# counter.net
KiCad netlist of a schematic drawn in EAGLE
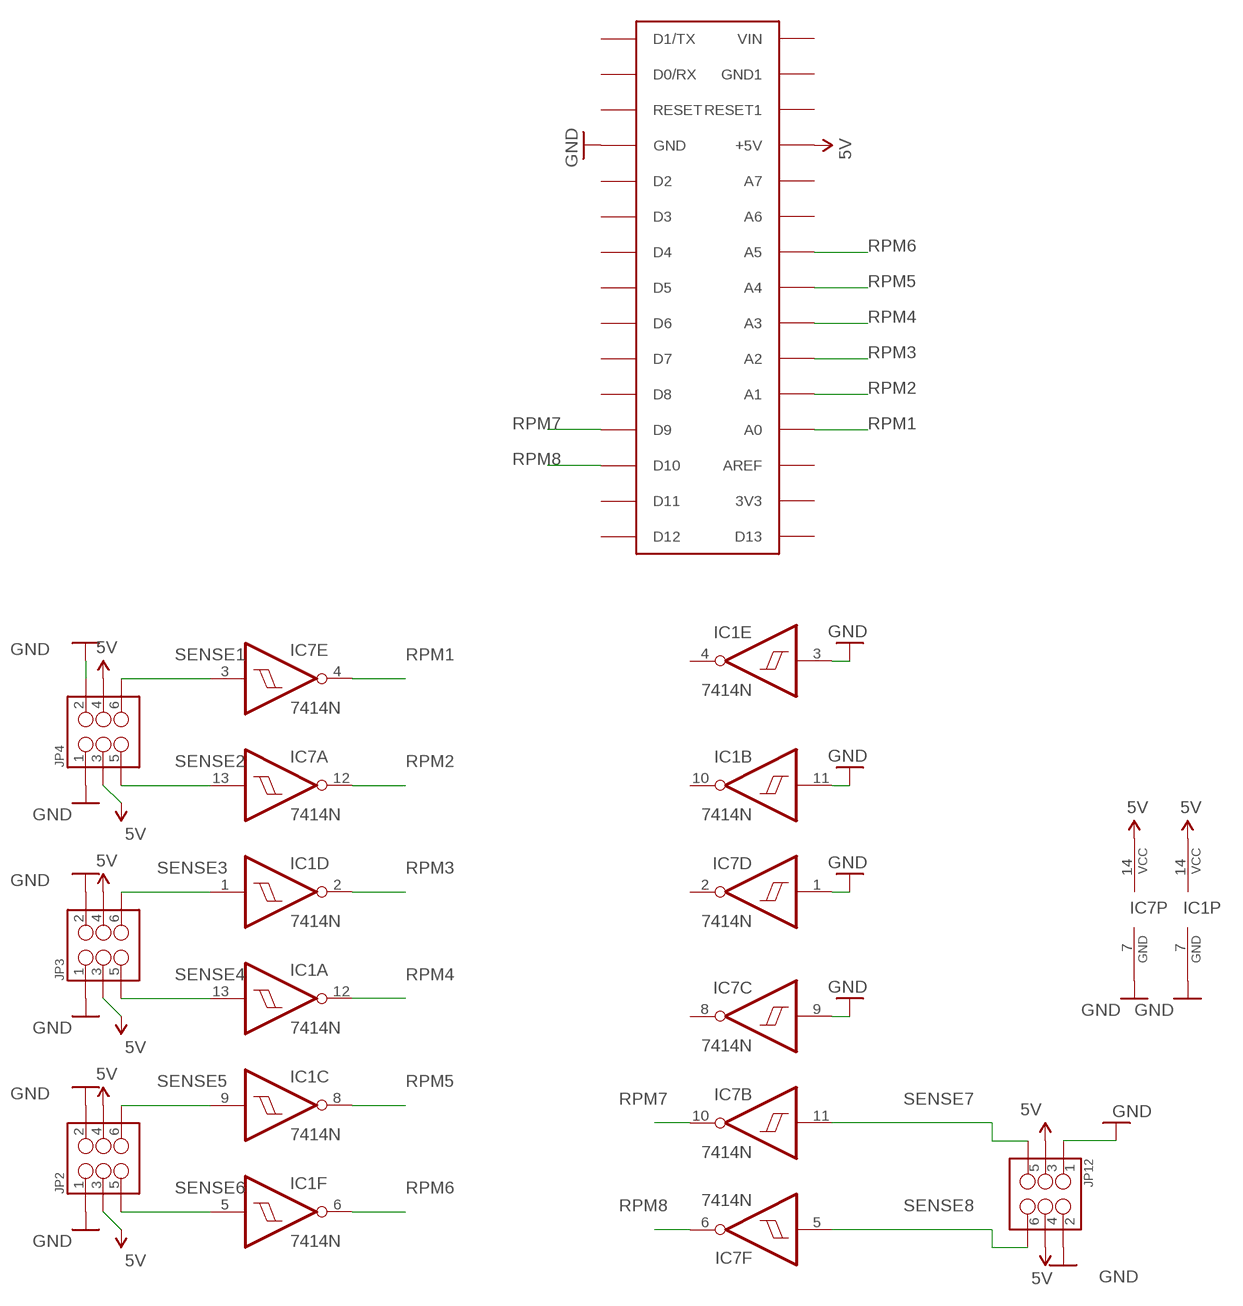
[diagram p0: schematic, sheet 1]

(export (version "E")
  (design (tool "Eeschema 10.0.6"))
  (components
    (comp (ref "IC1")
      (value "7414N")
      (footprint "eagle-import:DIL14")
      (libsource (lib "eagle-import") (part "7414N"))
    )
    (comp (ref "IC7")
      (value "7414N")
      (footprint "eagle-import:DIL14")
      (libsource (lib "eagle-import") (part "7414N"))
    )
    (comp (ref "JP2")
      (value "M03X2NO_SILK")
      (footprint "eagle-import:2X3-NS")
      (libsource (lib "eagle-import") (part "M03X2NO_SILK"))
    )
    (comp (ref "JP3")
      (value "M03X2NO_SILK")
      (footprint "eagle-import:2X3-NS")
      (libsource (lib "eagle-import") (part "M03X2NO_SILK"))
    )
    (comp (ref "JP4")
      (value "M03X2NO_SILK")
      (footprint "eagle-import:2X3-NS")
      (libsource (lib "eagle-import") (part "M03X2NO_SILK"))
    )
    (comp (ref "JP12")
      (value "M03X2NO_SILK")
      (footprint "eagle-import:2X3-NS")
      (libsource (lib "eagle-import") (part "M03X2NO_SILK"))
    )
    (comp (ref "U$1")
      (value "ARDUINONANO")
      (footprint "eagle-import:PDIP-32")
      (libsource (lib "eagle-import") (part "ARDUINONANO"))
    )
  )
  (nets
    (net (code "1") (name "/RPM1") (class "Default")
      (node (ref "IC7") (pin "4") (pinfunction "O_4") (pintype "output"))
      (node (ref "U$1") (pin "A0") (pinfunction "A0_A0") (pintype "bidirectional"))
    )
    (net (code "2") (name "/RPM2") (class "Default")
      (node (ref "IC7") (pin "12") (pinfunction "O_12") (pintype "output"))
      (node (ref "U$1") (pin "A1") (pinfunction "A1_A1") (pintype "bidirectional"))
    )
    (net (code "3") (name "/RPM3") (class "Default")
      (node (ref "IC1") (pin "2") (pinfunction "O_2") (pintype "output"))
      (node (ref "U$1") (pin "A2") (pinfunction "A2_A2") (pintype "bidirectional"))
    )
    (net (code "4") (name "/RPM4") (class "Default")
      (node (ref "IC1") (pin "12") (pinfunction "O_12") (pintype "output"))
      (node (ref "U$1") (pin "A3") (pinfunction "A3_A3") (pintype "bidirectional"))
    )
    (net (code "5") (name "/RPM5") (class "Default")
      (node (ref "IC1") (pin "8") (pinfunction "O_8") (pintype "output"))
      (node (ref "U$1") (pin "A4") (pinfunction "A4_A4") (pintype "bidirectional"))
    )
    (net (code "6") (name "/RPM6") (class "Default")
      (node (ref "IC1") (pin "6") (pinfunction "O_6") (pintype "output"))
      (node (ref "U$1") (pin "A5") (pinfunction "A5_A5") (pintype "bidirectional"))
    )
    (net (code "7") (name "/RPM7") (class "Default")
      (node (ref "IC7") (pin "10") (pinfunction "O_10") (pintype "output"))
      (node (ref "U$1") (pin "D9") (pinfunction "D9_D9") (pintype "bidirectional"))
    )
    (net (code "8") (name "/RPM8") (class "Default")
      (node (ref "IC7") (pin "6") (pinfunction "O_6") (pintype "output"))
      (node (ref "U$1") (pin "D10") (pinfunction "D10_D10") (pintype "bidirectional"))
    )
    (net (code "9") (name "/SENSE1") (class "Default")
      (node (ref "IC7") (pin "3") (pinfunction "I_3") (pintype "input"))
      (node (ref "JP4") (pin "6") (pinfunction "6_6") (pintype "bidirectional"))
    )
    (net (code "10") (name "/SENSE2") (class "Default")
      (node (ref "IC7") (pin "13") (pinfunction "I_13") (pintype "input"))
      (node (ref "JP4") (pin "5") (pinfunction "5_5") (pintype "bidirectional"))
    )
    (net (code "11") (name "/SENSE3") (class "Default")
      (node (ref "IC1") (pin "1") (pinfunction "I_1") (pintype "input"))
      (node (ref "JP3") (pin "6") (pinfunction "6_6") (pintype "bidirectional"))
    )
    (net (code "12") (name "/SENSE4") (class "Default")
      (node (ref "IC1") (pin "13") (pinfunction "I_13") (pintype "input"))
      (node (ref "JP3") (pin "5") (pinfunction "5_5") (pintype "bidirectional"))
    )
    (net (code "13") (name "/SENSE5") (class "Default")
      (node (ref "IC1") (pin "9") (pinfunction "I_9") (pintype "input"))
      (node (ref "JP2") (pin "6") (pinfunction "6_6") (pintype "bidirectional"))
    )
    (net (code "14") (name "/SENSE6") (class "Default")
      (node (ref "IC1") (pin "5") (pinfunction "I_5") (pintype "input"))
      (node (ref "JP2") (pin "5") (pinfunction "5_5") (pintype "bidirectional"))
    )
    (net (code "15") (name "/SENSE7") (class "Default")
      (node (ref "IC7") (pin "11") (pinfunction "I_11") (pintype "input"))
      (node (ref "JP12") (pin "5") (pinfunction "5_5") (pintype "bidirectional"))
    )
    (net (code "16") (name "/SENSE8") (class "Default")
      (node (ref "IC7") (pin "5") (pinfunction "I_5") (pintype "input"))
      (node (ref "JP12") (pin "6") (pinfunction "6_6") (pintype "bidirectional"))
    )
    (net (code "17") (name "5V") (class "Default")
      (node (ref "IC1") (pin "14") (pinfunction "VCC_14") (pintype "power_in"))
      (node (ref "IC7") (pin "14") (pinfunction "VCC_14") (pintype "power_in"))
      (node (ref "JP12") (pin "3") (pinfunction "3_3") (pintype "bidirectional"))
      (node (ref "JP12") (pin "4") (pinfunction "4_4") (pintype "bidirectional"))
      (node (ref "JP2") (pin "3") (pinfunction "3_3") (pintype "bidirectional"))
      (node (ref "JP2") (pin "4") (pinfunction "4_4") (pintype "bidirectional"))
      (node (ref "JP3") (pin "3") (pinfunction "3_3") (pintype "bidirectional"))
      (node (ref "JP3") (pin "4") (pinfunction "4_4") (pintype "bidirectional"))
      (node (ref "JP4") (pin "3") (pinfunction "3_3") (pintype "bidirectional"))
      (node (ref "JP4") (pin "4") (pinfunction "4_4") (pintype "bidirectional"))
      (node (ref "U$1") (pin "+5V") (pinfunction "+5V_+5V") (pintype "bidirectional"))
    )
    (net (code "18") (name "GND") (class "Default")
      (node (ref "IC1") (pin "11") (pinfunction "I_11") (pintype "input"))
      (node (ref "IC1") (pin "3") (pinfunction "I_3") (pintype "input"))
      (node (ref "IC1") (pin "7") (pinfunction "GND_7") (pintype "power_in"))
      (node (ref "IC7") (pin "1") (pinfunction "I_1") (pintype "input"))
      (node (ref "IC7") (pin "7") (pinfunction "GND_7") (pintype "power_in"))
      (node (ref "IC7") (pin "9") (pinfunction "I_9") (pintype "input"))
      (node (ref "JP12") (pin "1") (pinfunction "1_1") (pintype "bidirectional"))
      (node (ref "JP12") (pin "2") (pinfunction "2_2") (pintype "bidirectional"))
      (node (ref "JP2") (pin "1") (pinfunction "1_1") (pintype "bidirectional"))
      (node (ref "JP2") (pin "2") (pinfunction "2_2") (pintype "bidirectional"))
      (node (ref "JP3") (pin "1") (pinfunction "1_1") (pintype "bidirectional"))
      (node (ref "JP3") (pin "2") (pinfunction "2_2") (pintype "bidirectional"))
      (node (ref "JP4") (pin "1") (pinfunction "1_1") (pintype "bidirectional"))
      (node (ref "JP4") (pin "2") (pinfunction "2_2") (pintype "bidirectional"))
      (node (ref "U$1") (pin "GND") (pinfunction "GND_GND") (pintype "bidirectional"))
    )
    (net (code "19") (name "unconnected-(IC1B-O-Pad10)") (class "Default")
      (node (ref "IC1") (pin "10") (pinfunction "O_10") (pintype "output"))
    )
    (net (code "20") (name "unconnected-(IC1E-O-Pad4)") (class "Default")
      (node (ref "IC1") (pin "4") (pinfunction "O_4") (pintype "output"))
    )
    (net (code "21") (name "unconnected-(IC7C-O-Pad8)") (class "Default")
      (node (ref "IC7") (pin "8") (pinfunction "O_8") (pintype "output"))
    )
    (net (code "22") (name "unconnected-(IC7D-O-Pad2)") (class "Default")
      (node (ref "IC7") (pin "2") (pinfunction "O_2") (pintype "output"))
    )
    (net (code "23") (name "unconnected-(U$1-Pad3V3)") (class "Default")
      (node (ref "U$1") (pin "3V3") (pinfunction "3V3_3V3") (pintype "bidirectional"))
    )
    (net (code "24") (name "unconnected-(U$1-PadA6)") (class "Default")
      (node (ref "U$1") (pin "A6") (pinfunction "A6_A6") (pintype "bidirectional"))
    )
    (net (code "25") (name "unconnected-(U$1-PadA7)") (class "Default")
      (node (ref "U$1") (pin "A7") (pinfunction "A7_A7") (pintype "bidirectional"))
    )
    (net (code "26") (name "unconnected-(U$1-PadAREF)") (class "Default")
      (node (ref "U$1") (pin "AREF") (pinfunction "AREF_AREF") (pintype "bidirectional"))
    )
    (net (code "27") (name "unconnected-(U$1-PadD0{slash}RX)") (class "Default")
      (node (ref "U$1") (pin "D0/RX") (pinfunction "D0/RX_D0/RX") (pintype "bidirectional"))
    )
    (net (code "28") (name "unconnected-(U$1-PadD1{slash}TX)") (class "Default")
      (node (ref "U$1") (pin "D1/TX") (pinfunction "D1/TX_D1/TX") (pintype "bidirectional"))
    )
    (net (code "29") (name "unconnected-(U$1-PadD2)") (class "Default")
      (node (ref "U$1") (pin "D2") (pinfunction "D2_D2") (pintype "bidirectional"))
    )
    (net (code "30") (name "unconnected-(U$1-PadD3)") (class "Default")
      (node (ref "U$1") (pin "D3") (pinfunction "D3_D3") (pintype "bidirectional"))
    )
    (net (code "31") (name "unconnected-(U$1-PadD4)") (class "Default")
      (node (ref "U$1") (pin "D4") (pinfunction "D4_D4") (pintype "bidirectional"))
    )
    (net (code "32") (name "unconnected-(U$1-PadD5)") (class "Default")
      (node (ref "U$1") (pin "D5") (pinfunction "D5_D5") (pintype "bidirectional"))
    )
    (net (code "33") (name "unconnected-(U$1-PadD6)") (class "Default")
      (node (ref "U$1") (pin "D6") (pinfunction "D6_D6") (pintype "bidirectional"))
    )
    (net (code "34") (name "unconnected-(U$1-PadD7)") (class "Default")
      (node (ref "U$1") (pin "D7") (pinfunction "D7_D7") (pintype "bidirectional"))
    )
    (net (code "35") (name "unconnected-(U$1-PadD8)") (class "Default")
      (node (ref "U$1") (pin "D8") (pinfunction "D8_D8") (pintype "bidirectional"))
    )
    (net (code "36") (name "unconnected-(U$1-PadD11)") (class "Default")
      (node (ref "U$1") (pin "D11") (pinfunction "D11_D11") (pintype "bidirectional"))
    )
    (net (code "37") (name "unconnected-(U$1-PadD12)") (class "Default")
      (node (ref "U$1") (pin "D12") (pinfunction "D12_D12") (pintype "bidirectional"))
    )
    (net (code "38") (name "unconnected-(U$1-PadD13)") (class "Default")
      (node (ref "U$1") (pin "D13") (pinfunction "D13_D13") (pintype "bidirectional"))
    )
    (net (code "39") (name "unconnected-(U$1-PadGND1)") (class "Default")
      (node (ref "U$1") (pin "GND1") (pinfunction "GND1_GND1") (pintype "bidirectional"))
    )
    (net (code "40") (name "unconnected-(U$1-PadRESET)") (class "Default")
      (node (ref "U$1") (pin "RESET") (pinfunction "RESET_RESET") (pintype "bidirectional"))
    )
    (net (code "41") (name "unconnected-(U$1-PadRESET1)") (class "Default")
      (node (ref "U$1") (pin "RESET1") (pinfunction "RESET1_RESET1") (pintype "bidirectional"))
    )
    (net (code "42") (name "unconnected-(U$1-PadVIN)") (class "Default")
      (node (ref "U$1") (pin "VIN") (pinfunction "VIN_VIN") (pintype "bidirectional"))
    )
  )
)
